# tach.net
KiCad netlist of a schematic drawn in Altium Designer
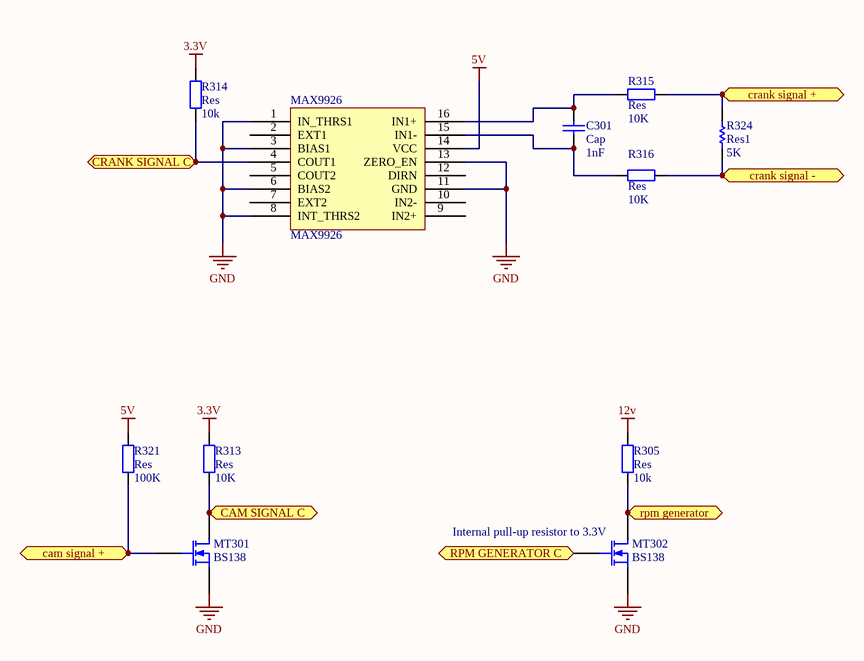
[diagram p0: tach.SchDoc]

(export (version "E")
  (design (tool "Eeschema 10.0.6"))
  (components
    (comp (ref "C301")
      (value "Cap")
      (footprint "1206 footprint")
      (fields (field (name "ALTIUM_VALUE") "1nF"))
      (libsource (lib "ArduinoNano") (part "Cap"))
    )
    (comp (ref "MAX9926")
      (value "MAX9926")
      (footprint "TSSOP-16")
      (libsource (lib "ArduinoNano") (part "MAX9926"))
    )
    (comp (ref "MT301") (value "BS138") (footprint "SOT23") (libsource (lib "ArduinoNano") (part "BS138")))
    (comp (ref "MT302") (value "BS138") (footprint "SOT23") (libsource (lib "ArduinoNano") (part "BS138")))
    (comp (ref "R305")
      (value "Res")
      (footprint "1206 footprint")
      (fields (field (name "ALTIUM_VALUE") "10k"))
      (libsource (lib "ArduinoNano") (part "Res"))
    )
    (comp (ref "R313")
      (value "Res")
      (footprint "1206 footprint")
      (fields (field (name "ALTIUM_VALUE") "10K"))
      (libsource (lib "ArduinoNano") (part "Res"))
    )
    (comp (ref "R314")
      (value "Res")
      (footprint "1206 footprint")
      (fields (field (name "ALTIUM_VALUE") "10k"))
      (libsource (lib "ArduinoNano") (part "Res"))
    )
    (comp (ref "R315")
      (value "Res")
      (footprint "1206 footprint")
      (fields (field (name "ALTIUM_VALUE") "10K"))
      (libsource (lib "") (part "Res_1"))
    )
    (comp (ref "R316")
      (value "Res")
      (footprint "1206 footprint")
      (fields (field (name "ALTIUM_VALUE") "10K"))
      (libsource (lib "") (part "Res_1"))
    )
    (comp (ref "R321")
      (value "Res")
      (footprint "1206 footprint")
      (fields (field (name "ALTIUM_VALUE") "100K"))
      (libsource (lib "ArduinoNano") (part "Res"))
    )
    (comp (ref "R324")
      (value "Res1")
      (footprint "AXIAL-0.3")
      (description "Resistor")
      (fields (field (name "ALTIUM_VALUE") "5K") (field (name "PUBLISHER") "Altium Limited"))
      (libsource (lib "Miscellaneous Devices") (part "Res1"))
    )
  )
  (nets
    (net (code "1") (name "/CAM SIGNAL C") (class "Default")
      (node (ref "MT301") (pin "3") (pinfunction "D_3") (pintype "passive"))
      (node (ref "R313") (pin "1") (pinfunction "1_1") (pintype "passive"))
    )
    (net (code "2") (name "/CRANK SIGNAL C") (class "Default")
      (node (ref "MAX9926") (pin "4") (pinfunction "COUT1_4") (pintype "passive"))
      (node (ref "R314") (pin "1") (pinfunction "1_1") (pintype "passive"))
    )
    (net (code "3") (name "/RPM GENERATOR C") (class "Default")
      (node (ref "MT302") (pin "1") (pinfunction "G_1") (pintype "passive"))
    )
    (net (code "4") (name "/cam signal +") (class "Default")
      (node (ref "MT301") (pin "1") (pinfunction "G_1") (pintype "passive"))
      (node (ref "R321") (pin "1") (pinfunction "1_1") (pintype "passive"))
    )
    (net (code "5") (name "/crank signal +") (class "Default")
      (node (ref "R315") (pin "2") (pinfunction "2_2") (pintype "passive"))
      (node (ref "R324") (pin "2") (pinfunction "2_2") (pintype "passive"))
    )
    (net (code "6") (name "/crank signal -") (class "Default")
      (node (ref "R316") (pin "2") (pinfunction "2_2") (pintype "passive"))
      (node (ref "R324") (pin "1") (pinfunction "1_1") (pintype "passive"))
    )
    (net (code "7") (name "/rpm generator") (class "Default")
      (node (ref "MT302") (pin "3") (pinfunction "D_3") (pintype "passive"))
      (node (ref "R305") (pin "1") (pinfunction "1_1") (pintype "passive"))
    )
    (net (code "8") (name "3.3V") (class "Default")
      (node (ref "R313") (pin "2") (pinfunction "2_2") (pintype "passive"))
      (node (ref "R314") (pin "2") (pinfunction "2_2") (pintype "passive"))
    )
    (net (code "9") (name "5V") (class "Default")
      (node (ref "MAX9926") (pin "14") (pinfunction "VCC_14") (pintype "passive"))
      (node (ref "R321") (pin "2") (pinfunction "2_2") (pintype "passive"))
    )
    (net (code "10") (name "12v") (class "Default")
      (node (ref "R305") (pin "2") (pinfunction "2_2") (pintype "passive"))
    )
    (net (code "11") (name "GND") (class "Default")
      (node (ref "MAX9926") (pin "1") (pinfunction "IN_THRS1_1") (pintype "passive"))
      (node (ref "MAX9926") (pin "11") (pinfunction "GND_11") (pintype "passive"))
      (node (ref "MAX9926") (pin "13") (pinfunction "ZERO_EN_13") (pintype "passive"))
      (node (ref "MAX9926") (pin "3") (pinfunction "BIAS1_3") (pintype "passive"))
      (node (ref "MAX9926") (pin "6") (pinfunction "BIAS2_6") (pintype "passive"))
      (node (ref "MAX9926") (pin "8") (pinfunction "INT_THRS2_8") (pintype "passive"))
      (node (ref "MT301") (pin "2") (pinfunction "S_2") (pintype "passive"))
      (node (ref "MT302") (pin "2") (pinfunction "S_2") (pintype "passive"))
    )
    (net (code "12") (name "Net-(MAX9926-IN1+)") (class "Default")
      (node (ref "C301") (pin "2") (pinfunction "2_2") (pintype "passive"))
      (node (ref "MAX9926") (pin "16") (pinfunction "IN1+_16") (pintype "passive"))
      (node (ref "R315") (pin "1") (pinfunction "1_1") (pintype "passive"))
    )
    (net (code "13") (name "Net-(MAX9926-IN1-)") (class "Default")
      (node (ref "C301") (pin "1") (pinfunction "1_1") (pintype "passive"))
      (node (ref "MAX9926") (pin "15") (pinfunction "IN1-_15") (pintype "passive"))
      (node (ref "R316") (pin "1") (pinfunction "1_1") (pintype "passive"))
    )
    (net (code "14") (name "unconnected-(MAX9926-COUT2-Pad5)") (class "Default")
      (node (ref "MAX9926") (pin "5") (pinfunction "COUT2_5") (pintype "passive"))
    )
    (net (code "15") (name "unconnected-(MAX9926-DIRN-Pad12)") (class "Default")
      (node (ref "MAX9926") (pin "12") (pinfunction "DIRN_12") (pintype "passive"))
    )
    (net (code "16") (name "unconnected-(MAX9926-EXT1-Pad2)") (class "Default")
      (node (ref "MAX9926") (pin "2") (pinfunction "EXT1_2") (pintype "passive"))
    )
    (net (code "17") (name "unconnected-(MAX9926-EXT2-Pad7)") (class "Default")
      (node (ref "MAX9926") (pin "7") (pinfunction "EXT2_7") (pintype "passive"))
    )
    (net (code "18") (name "unconnected-(MAX9926-IN2+-Pad9)") (class "Default")
      (node (ref "MAX9926") (pin "9") (pinfunction "IN2+_9") (pintype "passive"))
    )
    (net (code "19") (name "unconnected-(MAX9926-IN2--Pad10)") (class "Default")
      (node (ref "MAX9926") (pin "10") (pinfunction "IN2-_10") (pintype "passive"))
    )
  )
)
